# Thru-hole.net
KiCad netlist of a schematic drawn in EasyEDA
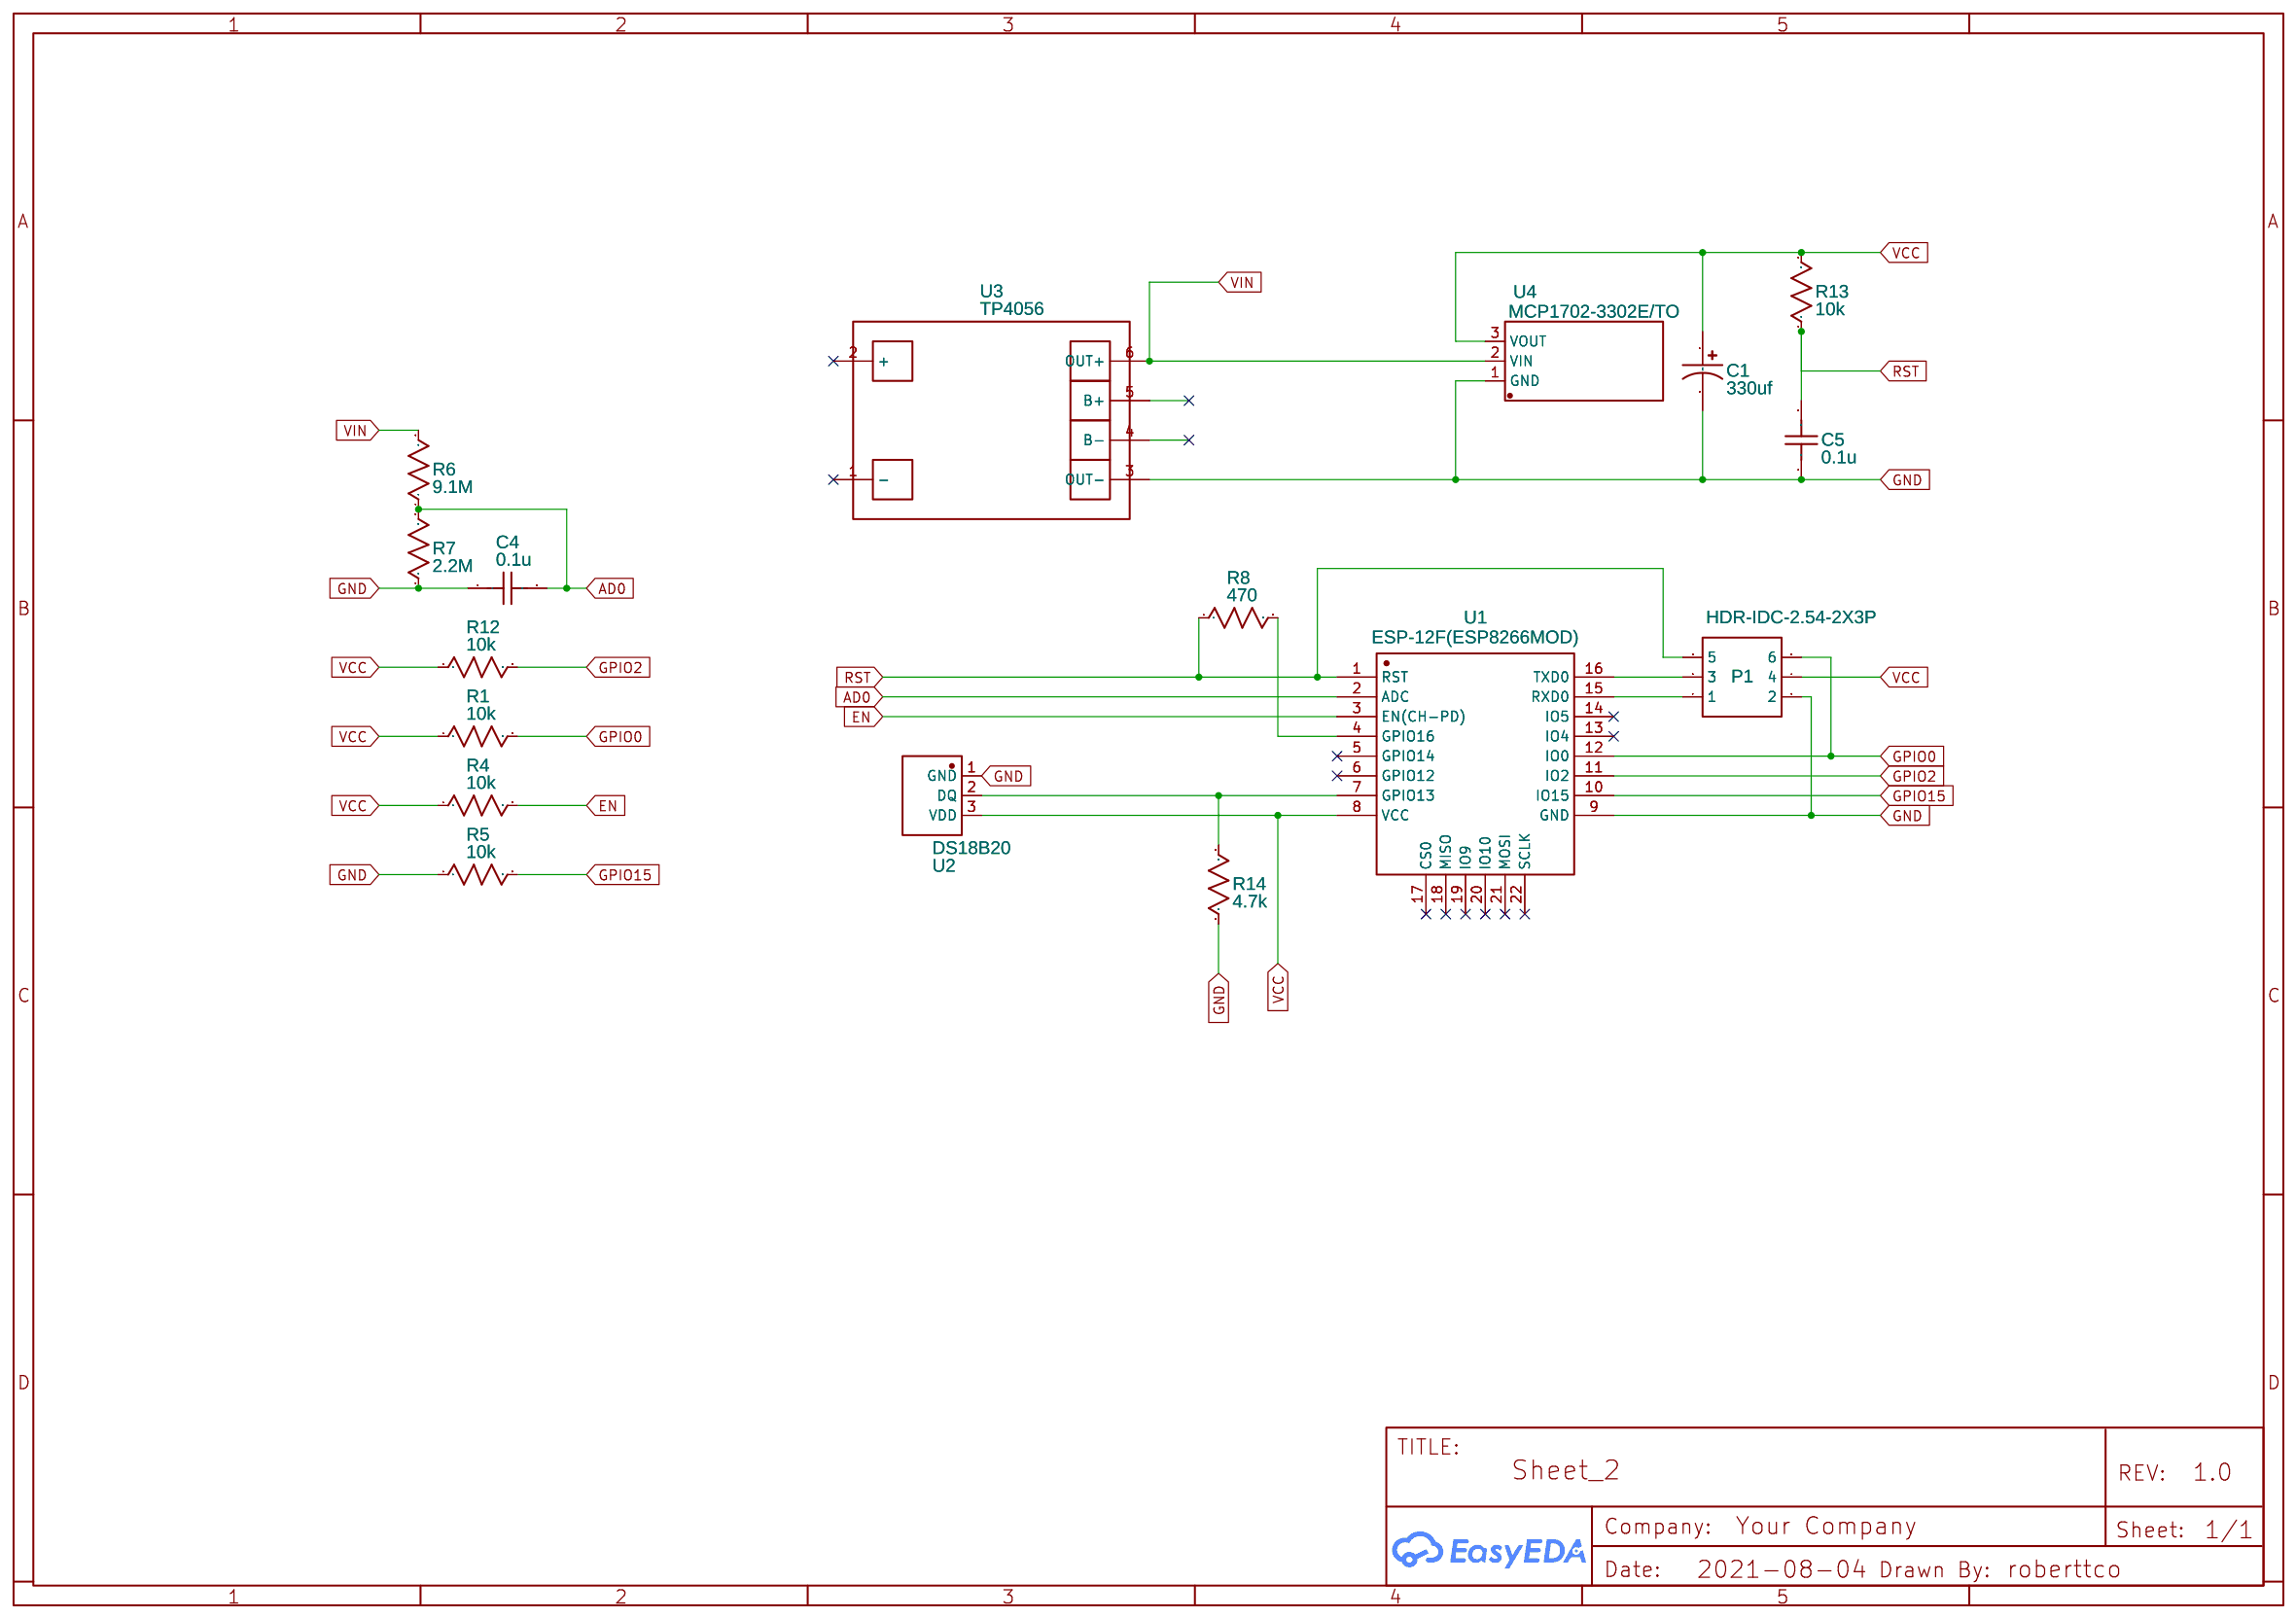
[diagram p0: schematic sheet]

(export (version "E")
  (design (tool "Eeschema 10.0.6"))
  (components
    (comp (ref "C1") (value "330uf") (libsource (lib "") (part "C_Tan_SMD_A_US")))
    (comp (ref "C4")
      (value "0.1u")
      (fields (field (name "BOM_Manufacturer Part") "GRM155R71C104KA88D"))
      (libsource (lib "") (part "C_0603_US_1"))
    )
    (comp (ref "C5")
      (value "0.1u")
      (fields (field (name "BOM_Manufacturer Part") "GRM155R71C104KA88D"))
      (libsource (lib "") (part "C_0603_US"))
    )
    (comp (ref "P1") (value "HDR-IDC-2.54-2X3P") (libsource (lib "") (part "HDR-IDC-2.54-2X3P")))
    (comp (ref "R1") (value "10k") (libsource (lib "") (part "R_0603_US")))
    (comp (ref "R4") (value "10k") (libsource (lib "") (part "R_0603_US")))
    (comp (ref "R5") (value "10k") (libsource (lib "") (part "R_0603_US")))
    (comp (ref "R6") (value "9.1M") (libsource (lib "") (part "R_0603_US_1")))
    (comp (ref "R7") (value "2.2M") (libsource (lib "") (part "R_0603_US_1")))
    (comp (ref "R8") (value "470") (libsource (lib "") (part "R_0603_US")))
    (comp (ref "R12") (value "10k") (libsource (lib "") (part "R_0603_US")))
    (comp (ref "R13") (value "10k") (libsource (lib "") (part "R_0603_US_1")))
    (comp (ref "R14") (value "4.7k") (libsource (lib "") (part "R_0603_US_1")))
    (comp (ref "U1")
      (value "ESP-12F(ESP8266MOD)")
      (fields (field (name "BOM_Supplier Part") "C82891"))
      (libsource (lib "") (part "ESP-12F(ESP8266MOD)"))
    )
    (comp (ref "U2") (value "DS18B20") (libsource (lib "") (part "DS18B20")))
    (comp (ref "U3") (value "TP4056") (libsource (lib "") (part "TP4056")))
    (comp (ref "U4")
      (value "MCP1702-3302E/TO")
      (fields (field (name "BOM_Supplier Part") "C220654"))
      (libsource (lib "") (part "MCP1702-3302E/TO"))
    )
  )
  (nets
    (net (code "1") (name "AD0") (class "Default")
      (node (ref "C4") (pin "2") (pinfunction "2_2") (pintype "unspecified"))
      (node (ref "R6") (pin "1") (pinfunction "1_1") (pintype "unspecified"))
      (node (ref "R7") (pin "2") (pinfunction "2_2") (pintype "unspecified"))
      (node (ref "U1") (pin "2") (pinfunction "ADC_2") (pintype "unspecified"))
    )
    (net (code "2") (name "EN") (class "Default")
      (node (ref "R4") (pin "2") (pinfunction "2_2") (pintype "unspecified"))
      (node (ref "U1") (pin "3") (pinfunction "EN(CH-PD)_3") (pintype "unspecified"))
    )
    (net (code "3") (name "GND") (class "Default")
      (node (ref "C1") (pin "2") (pinfunction "2_2") (pintype "unspecified"))
      (node (ref "C4") (pin "1") (pinfunction "1_1") (pintype "unspecified"))
      (node (ref "C5") (pin "1") (pinfunction "1_1") (pintype "unspecified"))
      (node (ref "P1") (pin "2") (pinfunction "2_2") (pintype "unspecified"))
      (node (ref "R14") (pin "1") (pinfunction "1_1") (pintype "unspecified"))
      (node (ref "R5") (pin "1") (pinfunction "1_1") (pintype "unspecified"))
      (node (ref "R7") (pin "1") (pinfunction "1_1") (pintype "unspecified"))
      (node (ref "U1") (pin "9") (pinfunction "GND_9") (pintype "unspecified"))
      (node (ref "U2") (pin "1") (pinfunction "GND_1") (pintype "unspecified"))
      (node (ref "U3") (pin "3") (pinfunction "OUT-_3") (pintype "unspecified"))
      (node (ref "U4") (pin "1") (pinfunction "GND_1") (pintype "unspecified"))
    )
    (net (code "4") (name "GPIO0") (class "Default")
      (node (ref "P1") (pin "6") (pinfunction "6_6") (pintype "unspecified"))
      (node (ref "R1") (pin "2") (pinfunction "2_2") (pintype "unspecified"))
      (node (ref "U1") (pin "12") (pinfunction "IO0_12") (pintype "unspecified"))
    )
    (net (code "5") (name "GPIO2") (class "Default")
      (node (ref "R12") (pin "2") (pinfunction "2_2") (pintype "unspecified"))
      (node (ref "U1") (pin "11") (pinfunction "IO2_11") (pintype "unspecified"))
    )
    (net (code "6") (name "GPIO15") (class "Default")
      (node (ref "R5") (pin "2") (pinfunction "2_2") (pintype "unspecified"))
      (node (ref "U1") (pin "10") (pinfunction "IO15_10") (pintype "unspecified"))
    )
    (net (code "7") (name "Net-(U1-GPIO13)") (class "Default")
      (node (ref "R14") (pin "2") (pinfunction "2_2") (pintype "unspecified"))
      (node (ref "U1") (pin "7") (pinfunction "GPIO13_7") (pintype "unspecified"))
      (node (ref "U2") (pin "2") (pinfunction "DQ_2") (pintype "unspecified"))
    )
    (net (code "8") (name "Net-(U1-GPIO16)") (class "Default")
      (node (ref "R8") (pin "2") (pinfunction "2_2") (pintype "unspecified"))
      (node (ref "U1") (pin "4") (pinfunction "GPIO16_4") (pintype "unspecified"))
    )
    (net (code "9") (name "Net-(U1-RXD0)") (class "Default")
      (node (ref "P1") (pin "1") (pinfunction "1_1") (pintype "unspecified"))
      (node (ref "U1") (pin "15") (pinfunction "RXD0_15") (pintype "unspecified"))
    )
    (net (code "10") (name "Net-(U1-TXD0)") (class "Default")
      (node (ref "P1") (pin "3") (pinfunction "3_3") (pintype "unspecified"))
      (node (ref "U1") (pin "16") (pinfunction "TXD0_16") (pintype "unspecified"))
    )
    (net (code "11") (name "RST") (class "Default")
      (node (ref "C5") (pin "2") (pinfunction "2_2") (pintype "unspecified"))
      (node (ref "P1") (pin "5") (pinfunction "5_5") (pintype "unspecified"))
      (node (ref "R13") (pin "1") (pinfunction "1_1") (pintype "unspecified"))
      (node (ref "R8") (pin "1") (pinfunction "1_1") (pintype "unspecified"))
      (node (ref "U1") (pin "1") (pinfunction "RST_1") (pintype "unspecified"))
    )
    (net (code "12") (name "VCC") (class "Default")
      (node (ref "C1") (pin "1") (pinfunction "1_1") (pintype "unspecified"))
      (node (ref "P1") (pin "4") (pinfunction "4_4") (pintype "unspecified"))
      (node (ref "R1") (pin "1") (pinfunction "1_1") (pintype "unspecified"))
      (node (ref "R12") (pin "1") (pinfunction "1_1") (pintype "unspecified"))
      (node (ref "R13") (pin "2") (pinfunction "2_2") (pintype "unspecified"))
      (node (ref "R4") (pin "1") (pinfunction "1_1") (pintype "unspecified"))
      (node (ref "U1") (pin "8") (pinfunction "VCC_8") (pintype "unspecified"))
      (node (ref "U2") (pin "3") (pinfunction "VDD_3") (pintype "unspecified"))
      (node (ref "U4") (pin "3") (pinfunction "VOUT_3") (pintype "unspecified"))
    )
    (net (code "13") (name "VIN") (class "Default")
      (node (ref "R6") (pin "2") (pinfunction "2_2") (pintype "unspecified"))
      (node (ref "U3") (pin "6") (pinfunction "OUT+_6") (pintype "unspecified"))
      (node (ref "U4") (pin "2") (pinfunction "VIN_2") (pintype "unspecified"))
    )
    (net (code "14") (name "unconnected-(U1-CS0-Pad17)") (class "Default")
      (node (ref "U1") (pin "17") (pinfunction "CS0_17") (pintype "unspecified+no_connect"))
    )
    (net (code "15") (name "unconnected-(U1-GPIO12-Pad6)") (class "Default")
      (node (ref "U1") (pin "6") (pinfunction "GPIO12_6") (pintype "unspecified+no_connect"))
    )
    (net (code "16") (name "unconnected-(U1-GPIO14-Pad5)") (class "Default")
      (node (ref "U1") (pin "5") (pinfunction "GPIO14_5") (pintype "unspecified+no_connect"))
    )
    (net (code "17") (name "unconnected-(U1-IO4-Pad13)") (class "Default")
      (node (ref "U1") (pin "13") (pinfunction "IO4_13") (pintype "unspecified+no_connect"))
    )
    (net (code "18") (name "unconnected-(U1-IO5-Pad14)") (class "Default")
      (node (ref "U1") (pin "14") (pinfunction "IO5_14") (pintype "unspecified+no_connect"))
    )
    (net (code "19") (name "unconnected-(U1-IO9-Pad19)") (class "Default")
      (node (ref "U1") (pin "19") (pinfunction "IO9_19") (pintype "unspecified+no_connect"))
    )
    (net (code "20") (name "unconnected-(U1-IO10-Pad20)") (class "Default")
      (node (ref "U1") (pin "20") (pinfunction "IO10_20") (pintype "unspecified+no_connect"))
    )
    (net (code "21") (name "unconnected-(U1-MISO-Pad18)") (class "Default")
      (node (ref "U1") (pin "18") (pinfunction "MISO_18") (pintype "unspecified+no_connect"))
    )
    (net (code "22") (name "unconnected-(U1-MOSI-Pad21)") (class "Default")
      (node (ref "U1") (pin "21") (pinfunction "MOSI_21") (pintype "unspecified+no_connect"))
    )
    (net (code "23") (name "unconnected-(U1-SCLK-Pad22)") (class "Default")
      (node (ref "U1") (pin "22") (pinfunction "SCLK_22") (pintype "unspecified+no_connect"))
    )
    (net (code "24") (name "unconnected-(U3-+-Pad2)") (class "Default")
      (node (ref "U3") (pin "2") (pinfunction "+_2") (pintype "unspecified+no_connect"))
    )
    (net (code "25") (name "unconnected-(U3---Pad1)") (class "Default")
      (node (ref "U3") (pin "1") (pinfunction "-_1") (pintype "unspecified+no_connect"))
    )
    (net (code "26") (name "unconnected-(U3-B+-Pad5)") (class "Default")
      (node (ref "U3") (pin "5") (pinfunction "B+_5") (pintype "unspecified+no_connect"))
    )
    (net (code "27") (name "unconnected-(U3-B--Pad4)") (class "Default")
      (node (ref "U3") (pin "4") (pinfunction "B-_4") (pintype "unspecified+no_connect"))
    )
  )
)
